# SW6124_A_B_C_Lighting_LED.net
KiCad netlist of a schematic drawn in Altium Designer
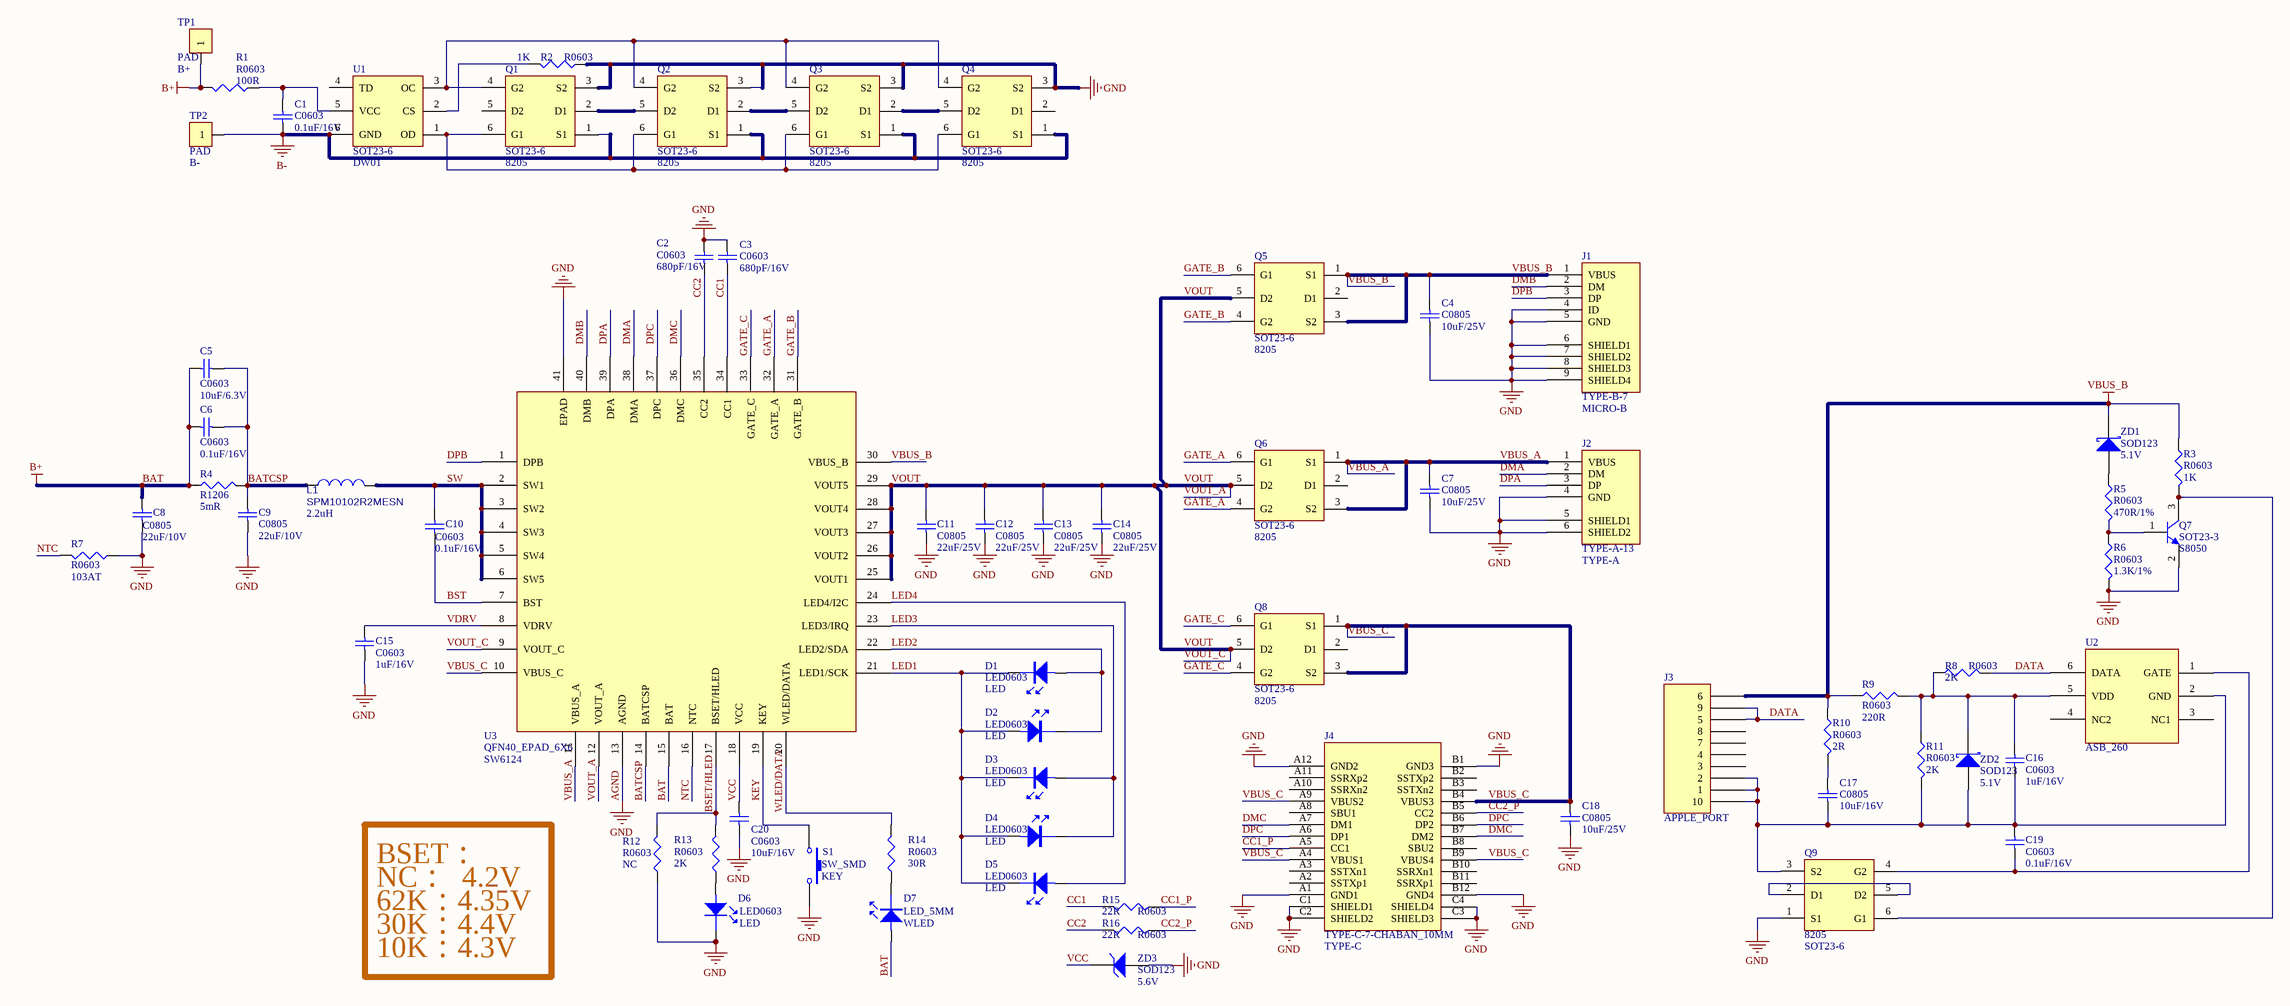
[diagram p0: SW6124+A+B+C+Lighting+LED.SchDoc]

(export (version "E")
  (design (tool "Eeschema 10.0.6"))
  (components
    (comp (ref "C1")
      (value "C0603")
      (footprint "C0603")
      (description "Capacitor")
      (fields (field (name "ALTIUM_VALUE") "0.1uF/16V") (field (name "PUBLISHER") "Altium Limited"))
      (libsource (lib "*") (part "Cap"))
    )
    (comp (ref "C2")
      (value "C0603")
      (footprint "C0603")
      (description "Capacitor")
      (fields (field (name "ALTIUM_VALUE") "680pF/16V") (field (name "PUBLISHER") "Altium Limited"))
      (libsource (lib "*") (part "CAP0603"))
    )
    (comp (ref "C3")
      (value "C0603")
      (footprint "C0603")
      (description "Capacitor")
      (fields (field (name "ALTIUM_VALUE") "680pF/16V") (field (name "PUBLISHER") "Altium Limited"))
      (libsource (lib "*") (part "CAP0603"))
    )
    (comp (ref "C4")
      (value "C0805")
      (footprint "C0805")
      (description "Capacitor")
      (fields (field (name "ALTIUM_VALUE") "10uF/25V") (field (name "PUBLISHER") "Altium Limited"))
      (libsource (lib "*") (part "CAP0603"))
    )
    (comp (ref "C5")
      (value "C0603")
      (footprint "C0603")
      (description "Capacitor")
      (fields (field (name "ALTIUM_VALUE") "10uF/6.3V") (field (name "PUBLISHER") "Altium Limited"))
      (libsource (lib "*") (part "CAP0603"))
    )
    (comp (ref "C6")
      (value "C0603")
      (footprint "C0603")
      (description "Capacitor")
      (fields (field (name "ALTIUM_VALUE") "0.1uF/16V") (field (name "PUBLISHER") "Altium Limited"))
      (libsource (lib "*") (part "CAP0603"))
    )
    (comp (ref "C7")
      (value "C0805")
      (footprint "C0805")
      (description "Capacitor")
      (fields (field (name "ALTIUM_VALUE") "10uF/25V") (field (name "PUBLISHER") "Altium Limited"))
      (libsource (lib "*") (part "CAP0603"))
    )
    (comp (ref "C8")
      (value "C0805")
      (footprint "C0805")
      (description "Capacitor")
      (fields (field (name "ALTIUM_VALUE") "22uF/10V") (field (name "PUBLISHER") "Altium Limited"))
      (libsource (lib "*") (part "CAP0805"))
    )
    (comp (ref "C9")
      (value "C0805")
      (footprint "C0805")
      (description "Capacitor")
      (fields (field (name "ALTIUM_VALUE") "22uF/10V") (field (name "PUBLISHER") "Altium Limited"))
      (libsource (lib "*") (part "CAP0805"))
    )
    (comp (ref "C10")
      (value "C0603")
      (footprint "C0603")
      (description "Capacitor")
      (fields (field (name "ALTIUM_VALUE") "0.1uF/16V") (field (name "PUBLISHER") "Altium Limited"))
      (libsource (lib "*") (part "CAP0603"))
    )
    (comp (ref "C11")
      (value "C0805")
      (footprint "C0805")
      (description "Capacitor")
      (fields (field (name "ALTIUM_VALUE") "22uF/25V") (field (name "PUBLISHER") "Altium Limited"))
      (libsource (lib "*") (part "CAP0805"))
    )
    (comp (ref "C12")
      (value "C0805")
      (footprint "C0805")
      (description "Capacitor")
      (fields (field (name "ALTIUM_VALUE") "22uF/25V") (field (name "PUBLISHER") "Altium Limited"))
      (libsource (lib "*") (part "CAP0805"))
    )
    (comp (ref "C13")
      (value "C0805")
      (footprint "C0805")
      (description "Capacitor")
      (fields (field (name "ALTIUM_VALUE") "22uF/25V") (field (name "PUBLISHER") "Altium Limited"))
      (libsource (lib "*") (part "CAP0805"))
    )
    (comp (ref "C14")
      (value "C0805")
      (footprint "C0805")
      (description "Capacitor")
      (fields (field (name "ALTIUM_VALUE") "22uF/25V") (field (name "PUBLISHER") "Altium Limited"))
      (libsource (lib "*") (part "CAP0805"))
    )
    (comp (ref "C15")
      (value "C0603")
      (footprint "C0603")
      (description "Capacitor")
      (fields (field (name "ALTIUM_VALUE") "1uF/16V") (field (name "PUBLISHER") "Altium Limited"))
      (libsource (lib "*") (part "CAP0603"))
    )
    (comp (ref "C16")
      (value "C0603")
      (footprint "C0603")
      (description "Capacitor")
      (fields (field (name "ALTIUM_VALUE") "1uF/16V") (field (name "PUBLISHER") "Altium Limited"))
      (libsource (lib "*") (part "CAP0805"))
    )
    (comp (ref "C17")
      (value "C0805")
      (footprint "C0805")
      (description "Capacitor")
      (fields (field (name "ALTIUM_VALUE") "10uF/16V") (field (name "PUBLISHER") "Altium Limited"))
      (libsource (lib "*") (part "CAP0805"))
    )
    (comp (ref "C18")
      (value "C0805")
      (footprint "C0805")
      (description "Capacitor")
      (fields (field (name "ALTIUM_VALUE") "10uF/25V") (field (name "PUBLISHER") "Altium Limited"))
      (libsource (lib "*") (part "CAP0603"))
    )
    (comp (ref "C19")
      (value "C0603")
      (footprint "C0603")
      (description "Capacitor")
      (fields (field (name "ALTIUM_VALUE") "0.1uF/16V") (field (name "PUBLISHER") "Altium Limited"))
      (libsource (lib "*") (part "CAP0805"))
    )
    (comp (ref "C20")
      (value "C0603")
      (footprint "C0603")
      (description "Capacitor")
      (fields (field (name "ALTIUM_VALUE") "10uF/16V") (field (name "PUBLISHER") "Altium Limited"))
      (libsource (lib "*") (part "CAP0603"))
    )
    (comp (ref "D1") (value "LED") (footprint "LED0603") (libsource (lib "*") (part "LED")))
    (comp (ref "D2") (value "LED") (footprint "LED0603") (libsource (lib "*") (part "LED")))
    (comp (ref "D3") (value "LED") (footprint "LED0603") (libsource (lib "*") (part "LED")))
    (comp (ref "D4") (value "LED") (footprint "LED0603") (libsource (lib "*") (part "LED")))
    (comp (ref "D5") (value "LED") (footprint "LED0603") (libsource (lib "*") (part "LED")))
    (comp (ref "D6") (value "LED") (footprint "LED0603") (libsource (lib "*") (part "LED")))
    (comp (ref "D7")
      (value "WLED")
      (footprint "LED_5MM")
      (fields (field (name "FOOTPRINF") "LED_5MM") (field (name "Comment") "LED_5MM"))
      (libsource (lib "*") (part "LED"))
    )
    (comp (ref "J1")
      (value "MICRO-B")
      (footprint "TYPE-B-7")
      (fields (field (name "FOOTPRINTF") "TYPE-B-7") (field (name "Comment") "USB_MICRO_B"))
      (libsource (lib "*") (part "USB_MICRO_B"))
    )
    (comp (ref "J2")
      (value "TYPE-A")
      (footprint "TYPE-A-13")
      (fields (field (name "FOOTPRINF") "TYPE-A-13") (field (name "Comment") "TYPE-A-1"))
      (libsource (lib "*") (part "TYPE-A-1"))
    )
    (comp (ref "J3") (value "APPLE_PORT") (libsource (lib "TEST") (part "APPLE_PORT")))
    (comp (ref "J4")
      (value "TYPE-C")
      (footprint "TYPE-C-7-CHABAN_10MM")
      (libsource (lib "*") (part "TYPE-C"))
    )
    (comp (ref "L1")
      (value "SPM10102R2MESN")
      (footprint "INDUCTOR_SPM1010")
      (fields (field (name "ALTIUM_VALUE") "2.2uH"))
      (libsource (lib "*") (part "INDUCTOR"))
    )
    (comp (ref "Q1")
      (value "8205")
      (footprint "SOT23-6")
      (fields (field (name "FOOTPRINF") "SOT23-6"))
      (libsource (lib "*") (part "8205B"))
    )
    (comp (ref "Q2")
      (value "8205")
      (footprint "SOT23-6")
      (fields (field (name "FOOTPRINF") "SOT23-6"))
      (libsource (lib "*") (part "8205B"))
    )
    (comp (ref "Q3")
      (value "8205")
      (footprint "SOT23-6")
      (fields (field (name "FOOTPRINF") "SOT23-6"))
      (libsource (lib "*") (part "8205B"))
    )
    (comp (ref "Q4")
      (value "8205")
      (footprint "SOT23-6")
      (fields (field (name "FOOTPRINF") "SOT23-6"))
      (libsource (lib "*") (part "8205B"))
    )
    (comp (ref "Q5")
      (value "8205")
      (footprint "SOT23-6")
      (fields (field (name "FOOTPRINF") "SOT23-6"))
      (libsource (lib "") (part "8205B_1"))
    )
    (comp (ref "Q6")
      (value "8205")
      (footprint "SOT23-6")
      (fields (field (name "FOOTPRINF") "SOT23-6"))
      (libsource (lib "") (part "8205B_1"))
    )
    (comp (ref "Q7")
      (value "S8050")
      (footprint "SOT23-3")
      (description "NPN General Purpose Amplifier")
      (fields (field (name "PUBLISHER") "Altium Limited"))
      (libsource (lib "Miscellaneous Devices") (part "2N3904"))
    )
    (comp (ref "Q8")
      (value "8205")
      (footprint "SOT23-6")
      (fields (field (name "FOOTPRINF") "SOT23-6"))
      (libsource (lib "") (part "8205B_1"))
    )
    (comp (ref "Q9")
      (value "8205")
      (footprint "SOT23-6")
      (fields (field (name "FOOTPRINF") "SOT23-6"))
      (libsource (lib "") (part "8205B_2"))
    )
    (comp (ref "R1")
      (value "R0603")
      (footprint "R0603")
      (description "Resistor")
      (fields (field (name "ALTIUM_VALUE") "100R") (field (name "PUBLISHER") "Altium Limited"))
      (libsource (lib "*") (part "Res3"))
    )
    (comp (ref "R2")
      (value "R0603")
      (footprint "R0603")
      (description "Resistor")
      (fields (field (name "ALTIUM_VALUE") "1K") (field (name "PUBLISHER") "Altium Limited"))
      (libsource (lib "*") (part "Res3"))
    )
    (comp (ref "R3")
      (value "R0603")
      (footprint "R0603")
      (description "Resistor")
      (fields (field (name "ALTIUM_VALUE") "1K") (field (name "PUBLISHER") "Altium Limited"))
      (libsource (lib "Miscellaneous Devices") (part "Res3"))
    )
    (comp (ref "R4")
      (value "R1206")
      (footprint "R1206")
      (description "Resistor")
      (fields (field (name "ALTIUM_VALUE") "5mR") (field (name "PUBLISHER") "Altium Limited"))
      (libsource (lib "*") (part "RES"))
    )
    (comp (ref "R5")
      (value "R0603")
      (footprint "R0603")
      (description "Resistor")
      (fields (field (name "ALTIUM_VALUE") "470R/1%") (field (name "PUBLISHER") "Altium Limited"))
      (libsource (lib "Miscellaneous Devices") (part "Res3"))
    )
    (comp (ref "R6")
      (value "R0603")
      (footprint "R0603")
      (description "Resistor")
      (fields (field (name "ALTIUM_VALUE") "1.3K/1%") (field (name "PUBLISHER") "Altium Limited"))
      (libsource (lib "Miscellaneous Devices") (part "Res3"))
    )
    (comp (ref "R7")
      (value "R0603")
      (footprint "R0603")
      (description "Resistor")
      (fields (field (name "ALTIUM_VALUE") "103AT") (field (name "PUBLISHER") "Altium Limited"))
      (libsource (lib "*") (part "RES"))
    )
    (comp (ref "R8")
      (value "R0603")
      (footprint "R0603")
      (description "Resistor")
      (fields (field (name "ALTIUM_VALUE") "2K") (field (name "PUBLISHER") "Altium Limited"))
      (libsource (lib "Miscellaneous Devices") (part "Res3"))
    )
    (comp (ref "R9")
      (value "R0603")
      (footprint "R0603")
      (description "Resistor")
      (fields (field (name "ALTIUM_VALUE") "220R") (field (name "PUBLISHER") "Altium Limited"))
      (libsource (lib "Miscellaneous Devices") (part "Res3"))
    )
    (comp (ref "R10")
      (value "R0603")
      (footprint "R0603")
      (description "Resistor")
      (fields (field (name "ALTIUM_VALUE") "2R") (field (name "PUBLISHER") "Altium Limited"))
      (libsource (lib "Miscellaneous Devices") (part "Res3"))
    )
    (comp (ref "R11")
      (value "R0603")
      (footprint "R0603")
      (description "Resistor")
      (fields (field (name "ALTIUM_VALUE") "2K") (field (name "PUBLISHER") "Altium Limited"))
      (libsource (lib "Miscellaneous Devices") (part "Res3"))
    )
    (comp (ref "R12")
      (value "R0603")
      (footprint "R0603")
      (description "Resistor")
      (fields (field (name "ALTIUM_VALUE") "NC") (field (name "PUBLISHER") "Altium Limited"))
      (libsource (lib "*") (part "RES"))
    )
    (comp (ref "R13")
      (value "R0603")
      (footprint "R0603")
      (description "Resistor")
      (fields (field (name "ALTIUM_VALUE") "2K") (field (name "PUBLISHER") "Altium Limited"))
      (libsource (lib "*") (part "RES"))
    )
    (comp (ref "R14")
      (value "R0603")
      (footprint "R0603")
      (description "Resistor")
      (fields (field (name "ALTIUM_VALUE") "30R") (field (name "PUBLISHER") "Altium Limited"))
      (libsource (lib "*") (part "RES"))
    )
    (comp (ref "R15")
      (value "R0603")
      (footprint "R0603")
      (description "Resistor")
      (fields (field (name "ALTIUM_VALUE") "22R") (field (name "PUBLISHER") "Altium Limited"))
      (libsource (lib "*") (part "RES"))
    )
    (comp (ref "R16")
      (value "R0603")
      (footprint "R0603")
      (description "Resistor")
      (fields (field (name "ALTIUM_VALUE") "22R") (field (name "PUBLISHER") "Altium Limited"))
      (libsource (lib "*") (part "RES"))
    )
    (comp (ref "S1")
      (value "KEY")
      (footprint "SW_SMD")
      (fields (field (name "FOOTPRINF") "SW_SMD"))
      (libsource (lib "*") (part "SW K"))
    )
    (comp (ref "TP1") (value "B+") (footprint "PAD") (libsource (lib "*") (part "Test Point")))
    (comp (ref "TP2") (value "B-") (footprint "PAD") (libsource (lib "") (part "Test Point_1")))
    (comp (ref "U1")
      (value "DW01")
      (footprint "SOT23-6")
      (fields (field (name "FOOTPRINF") "SOT23-6"))
      (libsource (lib "*") (part "DW01"))
    )
    (comp (ref "U2") (value "ASB_260") (footprint "SOT-23-") (libsource (lib "TEST") (part "ASB_260")))
    (comp (ref "U3")
      (value "SW6124")
      (footprint "QFN40_EPAD_6X6")
      (libsource (lib "TEST") (part "SW6106_AFC"))
    )
    (comp (ref "ZD1")
      (value "5.1V")
      (footprint "SOD123")
      (description "Schottky Rectifier")
      (fields (field (name "Comment") "Diode 11DQ03") (field (name "PUBLISHER") "Altium Limited"))
      (libsource (lib "Miscellaneous Devices") (part "Diode 11DQ03"))
    )
    (comp (ref "ZD2")
      (value "5.1V")
      (footprint "SOD123")
      (description "Schottky Rectifier")
      (fields (field (name "Comment") "Diode 11DQ03") (field (name "PUBLISHER") "Altium Limited"))
      (libsource (lib "Miscellaneous Devices") (part "Diode 11DQ03"))
    )
    (comp (ref "ZD3")
      (value "SOD123")
      (footprint "SOD-123")
      (description "Zener Diode")
      (fields (field (name "ALTIUM_UNNAMED_1") "5.6V"))
      (libsource (lib "Miscellaneous Devices") (part "D Zener"))
    )
  )
  (nets
    (net (code "1") (name "/BATCSP") (class "Default")
      (node (ref "C5") (pin "2") (pinfunction "2_2") (pintype "passive"))
      (node (ref "C6") (pin "2") (pinfunction "2_2") (pintype "passive"))
      (node (ref "C9") (pin "2") (pinfunction "2_2") (pintype "passive"))
      (node (ref "L1") (pin "1") (pinfunction "1_1") (pintype "passive"))
      (node (ref "R4") (pin "2") (pinfunction "2_2") (pintype "passive"))
      (node (ref "U3") (pin "14") (pinfunction "BATCSP_14") (pintype "passive"))
    )
    (net (code "2") (name "/BSET{slash}HLED") (class "Default")
      (node (ref "R12") (pin "2") (pinfunction "2_2") (pintype "passive"))
      (node (ref "R13") (pin "2") (pinfunction "2_2") (pintype "passive"))
      (node (ref "U3") (pin "17") (pinfunction "BSET/HLED_17") (pintype "passive"))
    )
    (net (code "3") (name "/BST") (class "Default")
      (node (ref "C10") (pin "1") (pinfunction "1_1") (pintype "passive"))
      (node (ref "U3") (pin "7") (pinfunction "BST_7") (pintype "passive"))
    )
    (net (code "4") (name "/CC1") (class "Default")
      (node (ref "C3") (pin "1") (pinfunction "1_1") (pintype "passive"))
      (node (ref "R15") (pin "2") (pinfunction "2_2") (pintype "passive"))
      (node (ref "U3") (pin "34") (pinfunction "CC1_34") (pintype "passive"))
    )
    (net (code "5") (name "/CC1_P") (class "Default")
      (node (ref "J4") (pin "A5") (pinfunction "CC1_A5") (pintype "passive"))
      (node (ref "R15") (pin "1") (pinfunction "1_1") (pintype "passive"))
    )
    (net (code "6") (name "/CC2") (class "Default")
      (node (ref "C2") (pin "1") (pinfunction "1_1") (pintype "passive"))
      (node (ref "R16") (pin "2") (pinfunction "2_2") (pintype "passive"))
      (node (ref "U3") (pin "35") (pinfunction "CC2_35") (pintype "passive"))
    )
    (net (code "7") (name "/CC2_P") (class "Default")
      (node (ref "J4") (pin "B5") (pinfunction "CC2_B5") (pintype "passive"))
      (node (ref "R16") (pin "1") (pinfunction "1_1") (pintype "passive"))
    )
    (net (code "8") (name "/DATA") (class "Default")
      (node (ref "J3") (pin "5") (pinfunction "5_5") (pintype "passive"))
      (node (ref "J3") (pin "9") (pinfunction "9_9") (pintype "passive"))
      (node (ref "R8") (pin "2") (pinfunction "2_2") (pintype "passive"))
      (node (ref "U2") (pin "6") (pinfunction "DATA_6") (pintype "passive"))
    )
    (net (code "9") (name "/DMA") (class "Default")
      (node (ref "J2") (pin "2") (pinfunction "DM_2") (pintype "passive"))
      (node (ref "U3") (pin "38") (pinfunction "DMA_38") (pintype "passive"))
    )
    (net (code "10") (name "/DMB") (class "Default")
      (node (ref "J1") (pin "2") (pinfunction "DM_2") (pintype "passive"))
      (node (ref "U3") (pin "40") (pinfunction "DMB_40") (pintype "passive"))
    )
    (net (code "11") (name "/DMC") (class "Default")
      (node (ref "J4") (pin "A7") (pinfunction "DM1_A7") (pintype "passive"))
      (node (ref "J4") (pin "B7") (pinfunction "DM2_B7") (pintype "passive"))
      (node (ref "U3") (pin "36") (pinfunction "DMC_36") (pintype "passive"))
    )
    (net (code "12") (name "/DPA") (class "Default")
      (node (ref "J2") (pin "3") (pinfunction "DP_3") (pintype "passive"))
      (node (ref "U3") (pin "39") (pinfunction "DPA_39") (pintype "passive"))
    )
    (net (code "13") (name "/DPB") (class "Default")
      (node (ref "J1") (pin "3") (pinfunction "DP_3") (pintype "passive"))
      (node (ref "U3") (pin "1") (pinfunction "DPB_1") (pintype "passive"))
    )
    (net (code "14") (name "/DPC") (class "Default")
      (node (ref "J4") (pin "A6") (pinfunction "DP1_A6") (pintype "passive"))
      (node (ref "J4") (pin "B6") (pinfunction "DP2_B6") (pintype "passive"))
      (node (ref "U3") (pin "37") (pinfunction "DPC_37") (pintype "passive"))
    )
    (net (code "15") (name "/GATE_A") (class "Default")
      (node (ref "Q6") (pin "4") (pinfunction "G2_4") (pintype "passive"))
      (node (ref "Q6") (pin "6") (pinfunction "G1_6") (pintype "passive"))
      (node (ref "U3") (pin "32") (pinfunction "GATE_A_32") (pintype "passive"))
    )
    (net (code "16") (name "/GATE_B") (class "Default")
      (node (ref "Q5") (pin "4") (pinfunction "G2_4") (pintype "passive"))
      (node (ref "Q5") (pin "6") (pinfunction "G1_6") (pintype "passive"))
      (node (ref "U3") (pin "31") (pinfunction "GATE_B_31") (pintype "passive"))
    )
    (net (code "17") (name "/GATE_C") (class "Default")
      (node (ref "Q8") (pin "4") (pinfunction "G2_4") (pintype "passive"))
      (node (ref "Q8") (pin "6") (pinfunction "G1_6") (pintype "passive"))
      (node (ref "U3") (pin "33") (pinfunction "GATE_C_33") (pintype "passive"))
    )
    (net (code "18") (name "/KEY") (class "Default")
      (node (ref "S1") (pin "1") (pinfunction "1_1") (pintype "passive"))
      (node (ref "U3") (pin "19") (pinfunction "KEY_19") (pintype "passive"))
    )
    (net (code "19") (name "/LED1") (class "Default")
      (node (ref "D1") (pin "2") (pinfunction "K_2") (pintype "passive"))
      (node (ref "D2") (pin "1") (pinfunction "A_1") (pintype "passive"))
      (node (ref "D3") (pin "2") (pinfunction "K_2") (pintype "passive"))
      (node (ref "D4") (pin "1") (pinfunction "A_1") (pintype "passive"))
      (node (ref "D5") (pin "2") (pinfunction "K_2") (pintype "passive"))
      (node (ref "U3") (pin "21") (pinfunction "LED1/SCK_21") (pintype "passive"))
    )
    (net (code "20") (name "/LED2") (class "Default")
      (node (ref "D1") (pin "1") (pinfunction "A_1") (pintype "passive"))
      (node (ref "D2") (pin "2") (pinfunction "K_2") (pintype "passive"))
      (node (ref "U3") (pin "22") (pinfunction "LED2/SDA_22") (pintype "passive"))
    )
    (net (code "21") (name "/LED3") (class "Default")
      (node (ref "D3") (pin "1") (pinfunction "A_1") (pintype "passive"))
      (node (ref "D4") (pin "2") (pinfunction "K_2") (pintype "passive"))
      (node (ref "U3") (pin "23") (pinfunction "LED3/IRQ_23") (pintype "passive"))
    )
    (net (code "22") (name "/LED4") (class "Default")
      (node (ref "D5") (pin "1") (pinfunction "A_1") (pintype "passive"))
      (node (ref "U3") (pin "24") (pinfunction "LED4/I2C_24") (pintype "passive"))
    )
    (net (code "23") (name "/NTC") (class "Default")
      (node (ref "R7") (pin "2") (pinfunction "2_2") (pintype "passive"))
      (node (ref "U3") (pin "16") (pinfunction "NTC_16") (pintype "passive"))
    )
    (net (code "24") (name "/SW") (class "Default")
      (node (ref "C10") (pin "2") (pinfunction "2_2") (pintype "passive"))
      (node (ref "L1") (pin "2") (pinfunction "2_2") (pintype "passive"))
      (node (ref "U3") (pin "2") (pinfunction "SW1_2") (pintype "passive"))
      (node (ref "U3") (pin "3") (pinfunction "SW2_3") (pintype "passive"))
      (node (ref "U3") (pin "4") (pinfunction "SW3_4") (pintype "passive"))
      (node (ref "U3") (pin "5") (pinfunction "SW4_5") (pintype "passive"))
      (node (ref "U3") (pin "6") (pinfunction "SW5_6") (pintype "passive"))
    )
    (net (code "25") (name "/VBUS_A") (class "Default")
      (node (ref "C7") (pin "2") (pinfunction "2_2") (pintype "passive"))
      (node (ref "J2") (pin "1") (pinfunction "VBUS_1") (pintype "passive"))
      (node (ref "Q6") (pin "1") (pinfunction "S1_1") (pintype "passive"))
      (node (ref "Q6") (pin "3") (pinfunction "S2_3") (pintype "passive"))
      (node (ref "U3") (pin "11") (pinfunction "VBUS_A_11") (pintype "passive"))
    )
    (net (code "26") (name "/VBUS_C") (class "Default")
      (node (ref "C18") (pin "2") (pinfunction "2_2") (pintype "passive"))
      (node (ref "J4") (pin "A4") (pinfunction "VBUS1_A4") (pintype "passive"))
      (node (ref "J4") (pin "A9") (pinfunction "VBUS2_A9") (pintype "passive"))
      (node (ref "J4") (pin "B4") (pinfunction "VBUS3_B4") (pintype "passive"))
      (node (ref "J4") (pin "B9") (pinfunction "VBUS4_B9") (pintype "passive"))
      (node (ref "Q8") (pin "1") (pinfunction "S1_1") (pintype "passive"))
      (node (ref "Q8") (pin "3") (pinfunction "S2_3") (pintype "passive"))
      (node (ref "U3") (pin "10") (pinfunction "VBUS_C_10") (pintype "passive"))
    )
    (net (code "27") (name "/VCC") (class "Default")
      (node (ref "C20") (pin "2") (pinfunction "2_2") (pintype "passive"))
      (node (ref "U3") (pin "18") (pinfunction "VCC_18") (pintype "passive"))
      (node (ref "ZD3") (pin "2") (pinfunction "K_2") (pintype "passive"))
    )
    (net (code "28") (name "/VDRV") (class "Default")
      (node (ref "C15") (pin "2") (pinfunction "2_2") (pintype "passive"))
      (node (ref "U3") (pin "8") (pinfunction "VDRV_8") (pintype "passive"))
    )
    (net (code "29") (name "/VOUT") (class "Default")
      (node (ref "C11") (pin "2") (pinfunction "2_2") (pintype "passive"))
      (node (ref "C12") (pin "2") (pinfunction "2_2") (pintype "passive"))
      (node (ref "C13") (pin "2") (pinfunction "2_2") (pintype "passive"))
      (node (ref "C14") (pin "2") (pinfunction "2_2") (pintype "passive"))
      (node (ref "Q5") (pin "5") (pinfunction "D2_5") (pintype "passive"))
      (node (ref "Q6") (pin "5") (pinfunction "D2_5") (pintype "passive"))
      (node (ref "Q8") (pin "5") (pinfunction "D2_5") (pintype "passive"))
      (node (ref "U3") (pin "12") (pinfunction "VOUT_A_12") (pintype "passive"))
      (node (ref "U3") (pin "25") (pinfunction "VOUT1_25") (pintype "passive"))
      (node (ref "U3") (pin "26") (pinfunction "VOUT2_26") (pintype "passive"))
      (node (ref "U3") (pin "27") (pinfunction "VOUT3_27") (pintype "passive"))
      (node (ref "U3") (pin "28") (pinfunction "VOUT4_28") (pintype "passive"))
      (node (ref "U3") (pin "29") (pinfunction "VOUT5_29") (pintype "passive"))
      (node (ref "U3") (pin "9") (pinfunction "VOUT_C_9") (pintype "passive"))
    )
    (net (code "30") (name "/WLED{slash}DATA") (class "Default")
      (node (ref "R14") (pin "2") (pinfunction "2_2") (pintype "passive"))
      (node (ref "U3") (pin "20") (pinfunction "WLED/DATA_20") (pintype "passive"))
    )
    (net (code "31") (name "B+") (class "Default")
      (node (ref "C5") (pin "1") (pinfunction "1_1") (pintype "passive"))
      (node (ref "C6") (pin "1") (pinfunction "1_1") (pintype "passive"))
      (node (ref "C8") (pin "2") (pinfunction "2_2") (pintype "passive"))
      (node (ref "D7") (pin "1") (pinfunction "A_1") (pintype "passive"))
      (node (ref "R1") (pin "2") (pinfunction "2_2") (pintype "passive"))
      (node (ref "R4") (pin "1") (pinfunction "1_1") (pintype "passive"))
      (node (ref "TP1") (pin "1") (pinfunction "1_1") (pintype "passive"))
      (node (ref "U3") (pin "15") (pinfunction "BAT_15") (pintype "passive"))
    )
    (net (code "32") (name "B-") (class "Default")
      (node (ref "C1") (pin "1") (pinfunction "1_1") (pintype "passive"))
      (node (ref "Q1") (pin "1") (pinfunction "S1_1") (pintype "passive"))
      (node (ref "Q2") (pin "1") (pinfunction "S1_1") (pintype "passive"))
      (node (ref "Q3") (pin "1") (pinfunction "S1_1") (pintype "passive"))
      (node (ref "Q4") (pin "1") (pinfunction "S1_1") (pintype "passive"))
      (node (ref "TP2") (pin "1") (pinfunction "1_1") (pintype "passive"))
      (node (ref "U1") (pin "6") (pinfunction "GND_6") (pintype "passive"))
    )
    (net (code "33") (name "GND") (class "Default")
      (node (ref "C11") (pin "1") (pinfunction "1_1") (pintype "passive"))
      (node (ref "C12") (pin "1") (pinfunction "1_1") (pintype "passive"))
      (node (ref "C13") (pin "1") (pinfunction "1_1") (pintype "passive"))
      (node (ref "C14") (pin "1") (pinfunction "1_1") (pintype "passive"))
      (node (ref "C15") (pin "1") (pinfunction "1_1") (pintype "passive"))
      (node (ref "C18") (pin "1") (pinfunction "1_1") (pintype "passive"))
      (node (ref "C2") (pin "2") (pinfunction "2_2") (pintype "passive"))
      (node (ref "C20") (pin "1") (pinfunction "1_1") (pintype "passive"))
      (node (ref "C3") (pin "2") (pinfunction "2_2") (pintype "passive"))
      (node (ref "C4") (pin "1") (pinfunction "1_1") (pintype "passive"))
      (node (ref "C7") (pin "1") (pinfunction "1_1") (pintype "passive"))
      (node (ref "C8") (pin "1") (pinfunction "1_1") (pintype "passive"))
      (node (ref "C9") (pin "1") (pinfunction "1_1") (pintype "passive"))
      (node (ref "D6") (pin "2") (pinfunction "K_2") (pintype "passive"))
      (node (ref "J1") (pin "4") (pinfunction "ID_4") (pintype "passive"))
      (node (ref "J1") (pin "5") (pinfunction "GND_5") (pintype "passive"))
      (node (ref "J1") (pin "6") (pinfunction "SHIELD1_6") (pintype "passive"))
      (node (ref "J1") (pin "7") (pinfunction "SHIELD2_7") (pintype "passive"))
      (node (ref "J1") (pin "8") (pinfunction "SHIELD3_8") (pintype "passive"))
      (node (ref "J1") (pin "9") (pinfunction "SHIELD4_9") (pintype "passive"))
      (node (ref "J2") (pin "4") (pinfunction "GND_4") (pintype "passive"))
      (node (ref "J2") (pin "5") (pinfunction "SHIELD1_5") (pintype "passive"))
      (node (ref "J2") (pin "6") (pinfunction "SHIELD2_6") (pintype "passive"))
      (node (ref "J4") (pin "A1") (pinfunction "GND1_A1") (pintype "passive"))
      (node (ref "J4") (pin "A12") (pinfunction "GND2_A12") (pintype "passive"))
      (node (ref "J4") (pin "B1") (pinfunction "GND3_B1") (pintype "passive"))
      (node (ref "J4") (pin "B12") (pinfunction "GND4_B12") (pintype "passive"))
      (node (ref "J4") (pin "C1") (pinfunction "SHIELD1_C1") (pintype "passive"))
      (node (ref "J4") (pin "C2") (pinfunction "SHIELD2_C2") (pintype "passive"))
      (node (ref "J4") (pin "C3") (pinfunction "SHIELD3_C3") (pintype "passive"))
      (node (ref "J4") (pin "C4") (pinfunction "SHIELD4_C4") (pintype "passive"))
      (node (ref "Q1") (pin "3") (pinfunction "S2_3") (pintype "passive"))
      (node (ref "Q2") (pin "3") (pinfunction "S2_3") (pintype "passive"))
      (node (ref "Q3") (pin "3") (pinfunction "S2_3") (pintype "passive"))
      (node (ref "Q4") (pin "3") (pinfunction "S2_3") (pintype "passive"))
      (node (ref "Q7") (pin "2") (pinfunction "E_2") (pintype "passive"))
      (node (ref "Q9") (pin "1") (pinfunction "S1_1") (pintype "passive"))
      (node (ref "R12") (pin "1") (pinfunction "1_1") (pintype "passive"))
      (node (ref "R2") (pin "1") (pinfunction "1_1") (pintype "passive"))
      (node (ref "R6") (pin "2") (pinfunction "2_2") (pintype "passive"))
      (node (ref "R7") (pin "1") (pinfunction "1_1") (pintype "passive"))
      (node (ref "S1") (pin "2") (pinfunction "2_2") (pintype "passive"))
      (node (ref "U3") (pin "13") (pinfunction "AGND_13") (pintype "passive"))
      (node (ref "U3") (pin "41") (pinfunction "EPAD_41") (pintype "passive"))
      (node (ref "ZD3") (pin "1") (pinfunction "A_1") (pintype "passive"))
    )
    (net (code "34") (name "Net-(C17-Pad2)") (class "Default")
      (node (ref "C17") (pin "2") (pinfunction "2_2") (pintype "passive"))
      (node (ref "R10") (pin "2") (pinfunction "2_2") (pintype "passive"))
    )
    (net (code "35") (name "Net-(D6-A)") (class "Default")
      (node (ref "D6") (pin "1") (pinfunction "A_1") (pintype "passive"))
      (node (ref "R13") (pin "1") (pinfunction "1_1") (pintype "passive"))
    )
    (net (code "36") (name "Net-(D7-K)") (class "Default")
      (node (ref "D7") (pin "2") (pinfunction "K_2") (pintype "passive"))
      (node (ref "R14") (pin "1") (pinfunction "1_1") (pintype "passive"))
    )
    (net (code "37") (name "Net-(Q1-D1)") (class "Default")
      (node (ref "Q1") (pin "2") (pinfunction "D1_2") (pintype "passive"))
      (node (ref "Q2") (pin "5") (pinfunction "D2_5") (pintype "passive"))
    )
    (net (code "38") (name "Net-(Q1-G1)") (class "Default")
      (node (ref "Q1") (pin "6") (pinfunction "G1_6") (pintype "passive"))
      (node (ref "Q2") (pin "6") (pinfunction "G1_6") (pintype "passive"))
      (node (ref "Q3") (pin "6") (pinfunction "G1_6") (pintype "passive"))
      (node (ref "Q4") (pin "6") (pinfunction "G1_6") (pintype "passive"))
      (node (ref "U1") (pin "1") (pinfunction "OD_1") (pintype "passive"))
    )
    (net (code "39") (name "Net-(Q1-G2)") (class "Default")
      (node (ref "Q1") (pin "4") (pinfunction "G2_4") (pintype "passive"))
      (node (ref "Q2") (pin "4") (pinfunction "G2_4") (pintype "passive"))
      (node (ref "Q3") (pin "4") (pinfunction "G2_4") (pintype "passive"))
      (node (ref "Q4") (pin "4") (pinfunction "G2_4") (pintype "passive"))
      (node (ref "U1") (pin "3") (pinfunction "OC_3") (pintype "passive"))
    )
    (net (code "40") (name "Net-(Q2-D1)") (class "Default")
      (node (ref "Q2") (pin "2") (pinfunction "D1_2") (pintype "passive"))
      (node (ref "Q3") (pin "5") (pinfunction "D2_5") (pintype "passive"))
    )
    (net (code "41") (name "Net-(Q3-D1)") (class "Default")
      (node (ref "Q3") (pin "2") (pinfunction "D1_2") (pintype "passive"))
      (node (ref "Q4") (pin "5") (pinfunction "D2_5") (pintype "passive"))
    )
    (net (code "42") (name "Net-(Q7-B)") (class "Default")
      (node (ref "Q7") (pin "1") (pinfunction "B_1") (pintype "passive"))
      (node (ref "R5") (pin "2") (pinfunction "2_2") (pintype "passive"))
      (node (ref "R6") (pin "1") (pinfunction "1_1") (pintype "passive"))
    )
    (net (code "43") (name "Net-(Q7-C)") (class "Default")
      (node (ref "Q7") (pin "3") (pinfunction "C_3") (pintype "passive"))
      (node (ref "Q9") (pin "6") (pinfunction "G1_6") (pintype "passive"))
      (node (ref "R3") (pin "2") (pinfunction "2_2") (pintype "passive"))
    )
    (net (code "44") (name "Net-(Q9-D1)") (class "Default")
      (node (ref "Q9") (pin "2") (pinfunction "D1_2") (pintype "passive"))
      (node (ref "Q9") (pin "5") (pinfunction "D2_5") (pintype "passive"))
    )
    (net (code "45") (name "Net-(Q9-G2)") (class "Default")
      (node (ref "C19") (pin "1") (pinfunction "1_1") (pintype "passive"))
      (node (ref "Q9") (pin "4") (pinfunction "G2_4") (pintype "passive"))
      (node (ref "U2") (pin "1") (pinfunction "GATE_1") (pintype "passive"))
    )
    (net (code "46") (name "Net-(Q9-S2)") (class "Default")
      (node (ref "C16") (pin "1") (pinfunction "1_1") (pintype "passive"))
      (node (ref "C17") (pin "1") (pinfunction "1_1") (pintype "passive"))
      (node (ref "C19") (pin "2") (pinfunction "2_2") (pintype "passive"))
      (node (ref "J3") (pin "1") (pinfunction "1_1") (pintype "passive"))
      (node (ref "J3") (pin "10") (pinfunction "10_10") (pintype "passive"))
      (node (ref "J3") (pin "2") (pinfunction "2_2") (pintype "passive"))
      (node (ref "Q9") (pin "3") (pinfunction "S2_3") (pintype "passive"))
      (node (ref "R11") (pin "2") (pinfunction "2_2") (pintype "passive"))
      (node (ref "U2") (pin "2") (pinfunction "GND_2") (pintype "passive"))
      (node (ref "ZD2") (pin "1") (pinfunction "A_1") (pintype "passive"))
    )
    (net (code "47") (name "Net-(U1-CS)") (class "Default")
      (node (ref "R2") (pin "2") (pinfunction "2_2") (pintype "passive"))
      (node (ref "U1") (pin "2") (pinfunction "CS_2") (pintype "passive"))
    )
    (net (code "48") (name "Net-(U1-VCC)") (class "Default")
      (node (ref "C1") (pin "2") (pinfunction "2_2") (pintype "passive"))
      (node (ref "R1") (pin "1") (pinfunction "1_1") (pintype "passive"))
      (node (ref "U1") (pin "5") (pinfunction "VCC_5") (pintype "passive"))
    )
    (net (code "49") (name "Net-(U2-VDD)") (class "Default")
      (node (ref "C16") (pin "2") (pinfunction "2_2") (pintype "passive"))
      (node (ref "R11") (pin "1") (pinfunction "1_1") (pintype "passive"))
      (node (ref "R8") (pin "1") (pinfunction "1_1") (pintype "passive"))
      (node (ref "R9") (pin "2") (pinfunction "2_2") (pintype "passive"))
      (node (ref "U2") (pin "5") (pinfunction "VDD_5") (pintype "passive"))
      (node (ref "ZD2") (pin "2") (pinfunction "K_2") (pintype "passive"))
    )
    (net (code "50") (name "Net-(ZD1-A)") (class "Default")
      (node (ref "R5") (pin "1") (pinfunction "1_1") (pintype "passive"))
      (node (ref "ZD1") (pin "1") (pinfunction "A_1") (pintype "passive"))
    )
    (net (code "51") (name "VBUS_B") (class "Default")
      (node (ref "C4") (pin "2") (pinfunction "2_2") (pintype "passive"))
      (node (ref "J1") (pin "1") (pinfunction "VBUS_1") (pintype "passive"))
      (node (ref "J3") (pin "6") (pinfunction "6_6") (pintype "passive"))
      (node (ref "Q5") (pin "1") (pinfunction "S1_1") (pintype "passive"))
      (node (ref "Q5") (pin "3") (pinfunction "S2_3") (pintype "passive"))
      (node (ref "R10") (pin "1") (pinfunction "1_1") (pintype "passive"))
      (node (ref "R3") (pin "1") (pinfunction "1_1") (pintype "passive"))
      (node (ref "R9") (pin "1") (pinfunction "1_1") (pintype "passive"))
      (node (ref "U3") (pin "30") (pinfunction "VBUS_B_30") (pintype "passive"))
      (node (ref "ZD1") (pin "2") (pinfunction "K_2") (pintype "passive"))
    )
    (net (code "52") (name "unconnected-(J3-Pad3)") (class "Default")
      (node (ref "J3") (pin "3") (pinfunction "3_3") (pintype "passive"))
    )
    (net (code "53") (name "unconnected-(J3-Pad4)") (class "Default")
      (node (ref "J3") (pin "4") (pinfunction "4_4") (pintype "passive"))
    )
    (net (code "54") (name "unconnected-(J3-Pad7)") (class "Default")
      (node (ref "J3") (pin "7") (pinfunction "7_7") (pintype "passive"))
    )
    (net (code "55") (name "unconnected-(J3-Pad8)") (class "Default")
      (node (ref "J3") (pin "8") (pinfunction "8_8") (pintype "passive"))
    )
    (net (code "56") (name "unconnected-(J4-SBU1-PadA8)") (class "Default")
      (node (ref "J4") (pin "A8") (pinfunction "SBU1_A8") (pintype "passive"))
    )
    (net (code "57") (name "unconnected-(J4-SBU2-PadB8)") (class "Default")
      (node (ref "J4") (pin "B8") (pinfunction "SBU2_B8") (pintype "passive"))
    )
    (net (code "58") (name "unconnected-(J4-SSRXn1-PadB10)") (class "Default")
      (node (ref "J4") (pin "B10") (pinfunction "SSRXn1_B10") (pintype "passive"))
    )
    (net (code "59") (name "unconnected-(J4-SSRXn2-PadA10)") (class "Default")
      (node (ref "J4") (pin "A10") (pinfunction "SSRXn2_A10") (pintype "passive"))
    )
    (net (code "60") (name "unconnected-(J4-SSRXp1-PadB11)") (class "Default")
      (node (ref "J4") (pin "B11") (pinfunction "SSRXp1_B11") (pintype "passive"))
    )
    (net (code "61") (name "unconnected-(J4-SSRXp2-PadA11)") (class "Default")
      (node (ref "J4") (pin "A11") (pinfunction "SSRXp2_A11") (pintype "passive"))
    )
    (net (code "62") (name "unconnected-(J4-SSTXn1-PadA3)") (class "Default")
      (node (ref "J4") (pin "A3") (pinfunction "SSTXn1_A3") (pintype "passive"))
    )
    (net (code "63") (name "unconnected-(J4-SSTXn2-PadB3)") (class "Default")
      (node (ref "J4") (pin "B3") (pinfunction "SSTXn2_B3") (pintype "passive"))
    )
    (net (code "64") (name "unconnected-(J4-SSTXp1-PadA2)") (class "Default")
      (node (ref "J4") (pin "A2") (pinfunction "SSTXp1_A2") (pintype "passive"))
    )
    (net (code "65") (name "unconnected-(J4-SSTXp2-PadB2)") (class "Default")
      (node (ref "J4") (pin "B2") (pinfunction "SSTXp2_B2") (pintype "passive"))
    )
    (net (code "66") (name "unconnected-(Q1-D2-Pad5)") (class "Default")
      (node (ref "Q1") (pin "5") (pinfunction "D2_5") (pintype "passive"))
    )
    (net (code "67") (name "unconnected-(Q4-D1-Pad2)") (class "Default")
      (node (ref "Q4") (pin "2") (pinfunction "D1_2") (pintype "passive"))
    )
    (net (code "68") (name "unconnected-(Q5-D1-Pad2)") (class "Default")
      (node (ref "Q5") (pin "2") (pinfunction "D1_2") (pintype "passive"))
    )
    (net (code "69") (name "unconnected-(Q6-D1-Pad2)") (class "Default")
      (node (ref "Q6") (pin "2") (pinfunction "D1_2") (pintype "passive"))
    )
    (net (code "70") (name "unconnected-(Q8-D1-Pad2)") (class "Default")
      (node (ref "Q8") (pin "2") (pinfunction "D1_2") (pintype "passive"))
    )
    (net (code "71") (name "unconnected-(U1-TD-Pad4)") (class "Default")
      (node (ref "U1") (pin "4") (pinfunction "TD_4") (pintype "passive"))
    )
    (net (code "72") (name "unconnected-(U2-NC1-Pad3)") (class "Default")
      (node (ref "U2") (pin "3") (pinfunction "NC1_3") (pintype "passive"))
    )
    (net (code "73") (name "unconnected-(U2-NC2-Pad4)") (class "Default")
      (node (ref "U2") (pin "4") (pinfunction "NC2_4") (pintype "passive"))
    )
  )
)
